# LMAT_AMT_MAG.net
KiCad netlist of a schematic drawn in Altium Designer
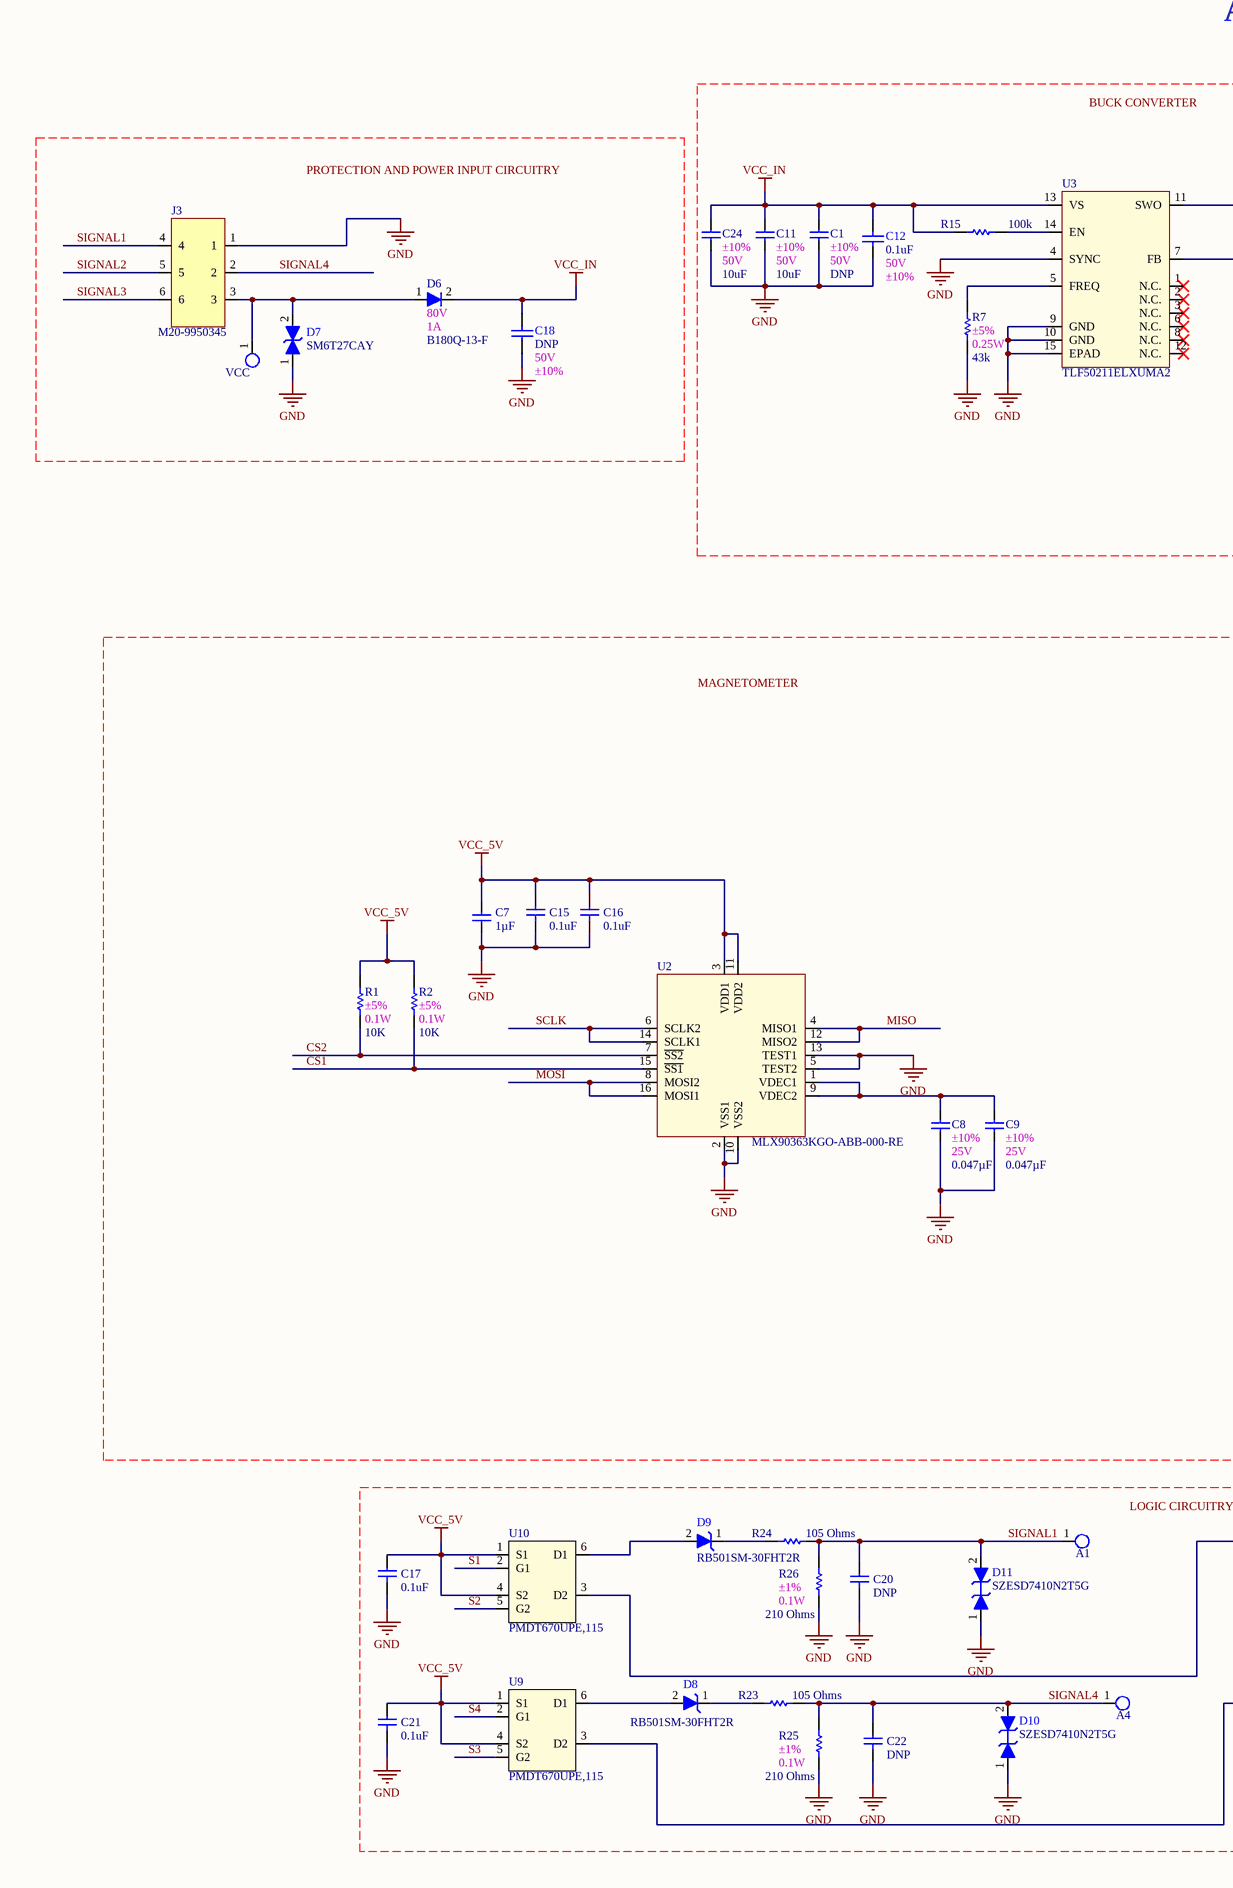
[diagram p0: LMAT_AMT_MAG.SchDoc, left]
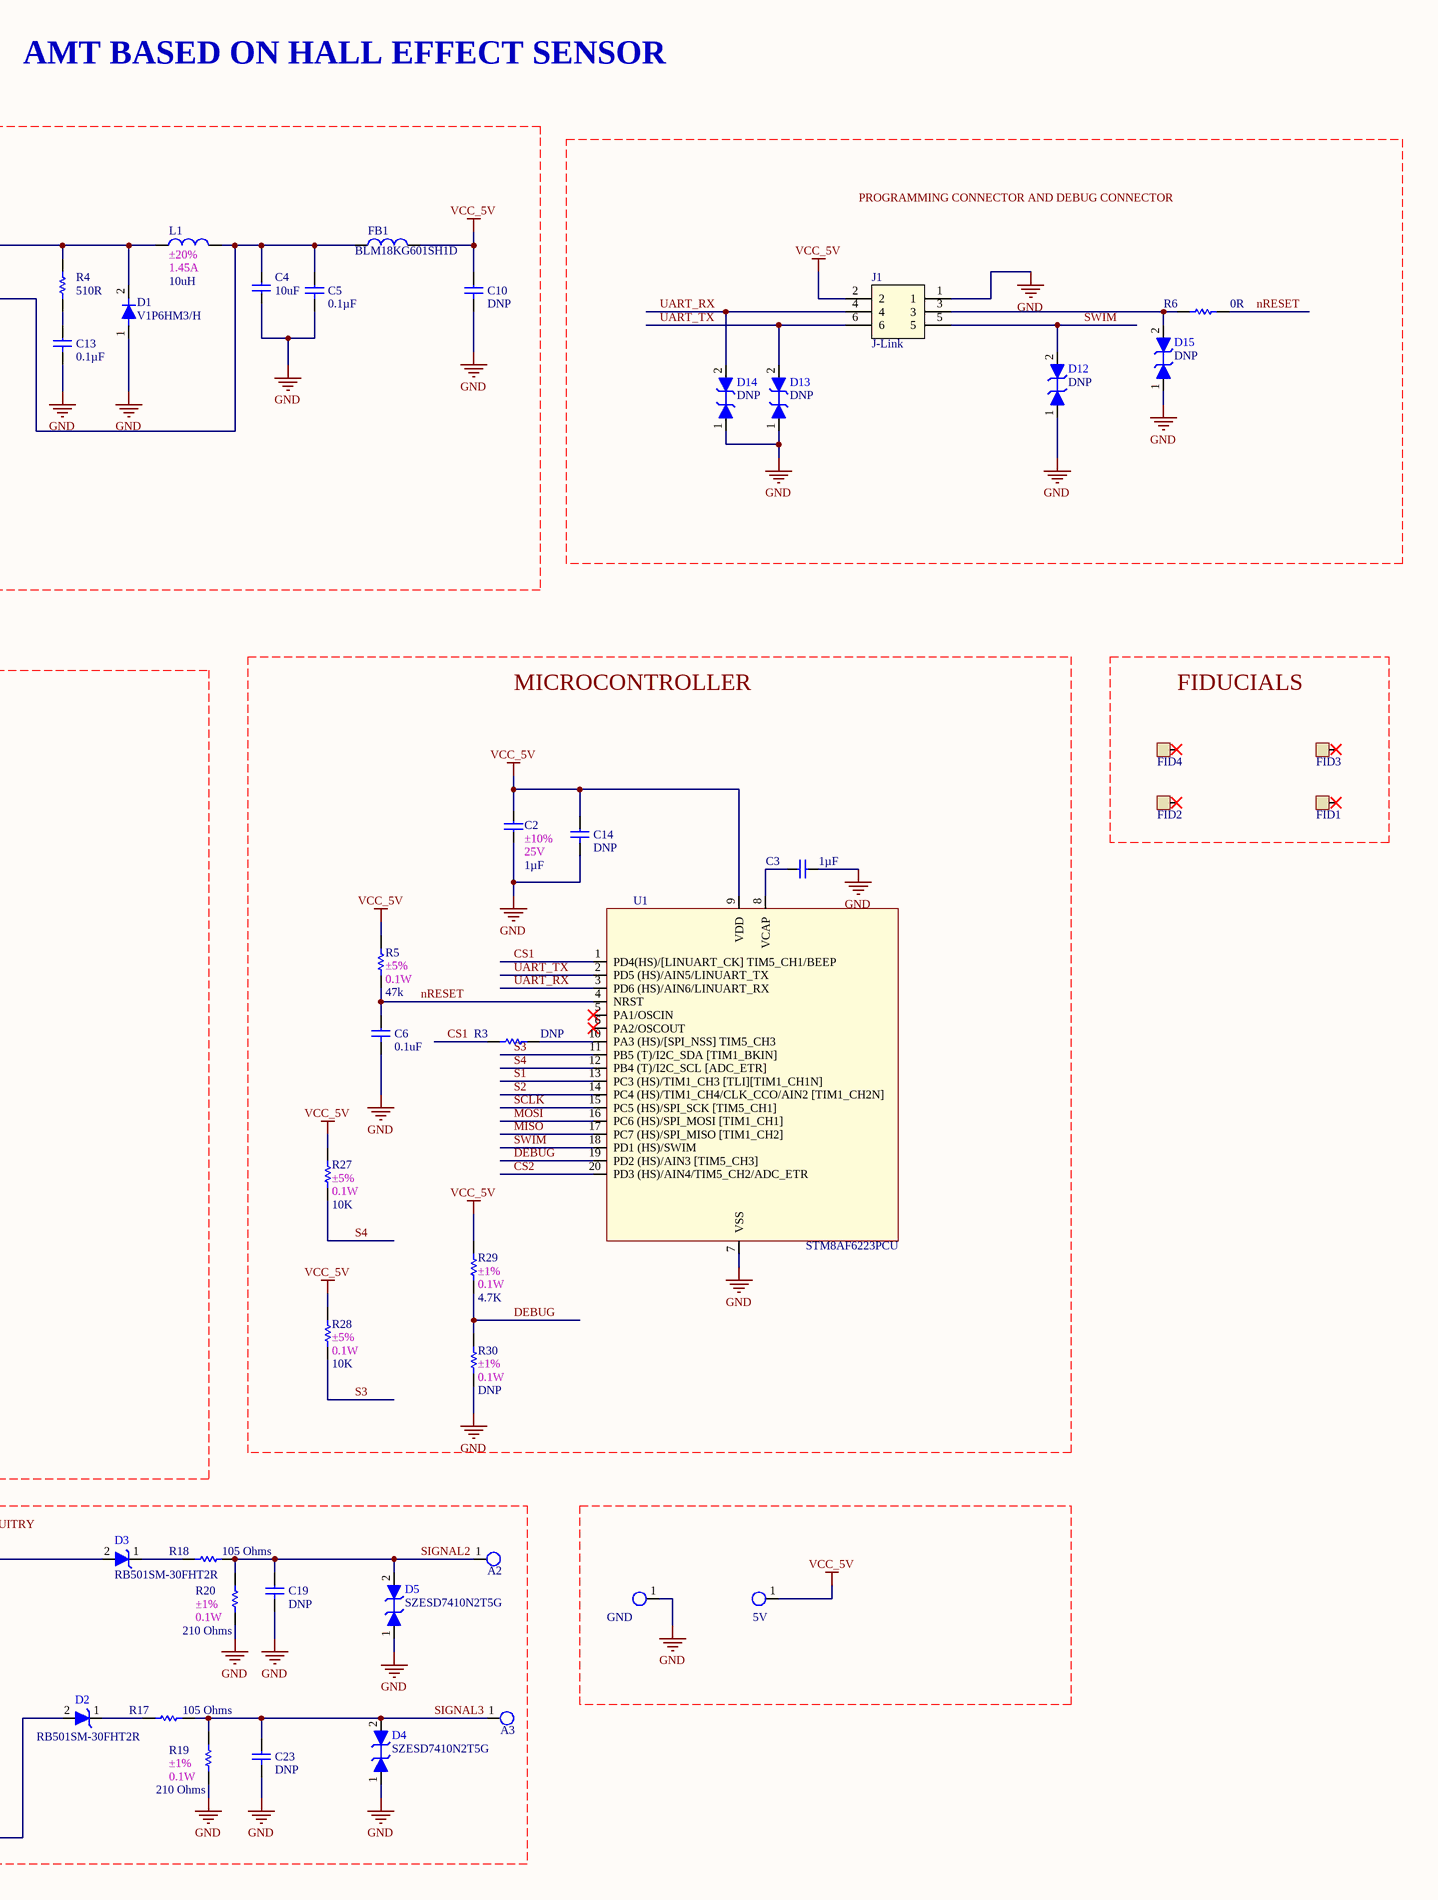
[diagram p1: LMAT_AMT_MAG.SchDoc, right]

(export (version "E")
  (design (tool "Eeschema 10.0.6"))
  (components
    (comp (ref "5V")
      (value "Test Point- 35mil")
      (footprint "Master_Library:TP_35M_DIA")
      (fields (field (name "INTERNAL PART NUMBER") "EMS-TP35MIL-S"))
      (libsource (lib "Integrated_Master_Library") (part "EMS-TP35MIL-S"))
    )
    (comp (ref "A1")
      (value "Test Point- 35mil")
      (footprint "Master_Library:TP_35M_DIA")
      (fields (field (name "INTERNAL PART NUMBER") "EMS-TP35MIL-S"))
      (libsource (lib "Integrated_Master_Library") (part "EMS-TP35MIL-S"))
    )
    (comp (ref "A2")
      (value "Test Point- 35mil")
      (footprint "Master_Library:TP_35M_DIA")
      (fields (field (name "INTERNAL PART NUMBER") "EMS-TP35MIL-S"))
      (libsource (lib "Integrated_Master_Library") (part "EMS-TP35MIL-S"))
    )
    (comp (ref "A3")
      (value "Test Point- 35mil")
      (footprint "Master_Library:TP_35M_DIA")
      (fields (field (name "INTERNAL PART NUMBER") "EMS-TP35MIL-S"))
      (libsource (lib "Integrated_Master_Library") (part "EMS-TP35MIL-S"))
    )
    (comp (ref "A4")
      (value "Test Point- 35mil")
      (footprint "Master_Library:TP_35M_DIA")
      (fields (field (name "INTERNAL PART NUMBER") "EMS-TP35MIL-S"))
      (libsource (lib "Integrated_Master_Library") (part "EMS-TP35MIL-S"))
    )
    (comp (ref "C1")
      (value "DNP")
      (footprint "Master_Library:SMDC1210")
      (description "CAP CER 10UF 50V X7R 1210")
      (fields
        (field (name "MANUFACTURER") "Taiyo Yuden")
        (field (name "VENDOR PART NUMBER") "587-6026-1-ND")
        (field (name "2ND AUXILIARY FIELD") "±10%")
        (field (name "1ST AUXILIARY FIELD") "50V")
      )
      (libsource (lib "Automobile-ML") (part "ECA10U0L50V0-SH"))
    )
    (comp (ref "C2")
      (value "1µF")
      (footprint "Masterlib_auto:SMDC0603")
      (description "CAP CER 1UF 25V X7R 0603")
      (fields
        (field (name "MANUFACTURER") "TDK Corporation")
        (field (name "VENDOR PART NUMBER") "445-173628-1-ND")
        (field (name "2ND AUXILIARY FIELD") "±10%")
        (field (name "1ST AUXILIARY FIELD") "25V")
      )
      (libsource (lib "Integrated_Master_Library (3)") (part "ECA1U00L25V0-SC"))
    )
    (comp (ref "C3")
      (value "1µF")
      (footprint "Masterlib_auto:SMDC0603")
      (description "CAP CER 1UF 25V X7R 0603")
      (fields
        (field (name "MANUFACTURER") "TDK Corporation")
        (field (name "VENDOR PART NUMBER") "445-173628-1-ND")
      )
      (libsource (lib "Integrated_Master_Library (3)") (part "ECA1U00L25V0-SC"))
    )
    (comp (ref "C4")
      (value "10uF")
      (footprint "Master_Library:SMDC1210")
      (description "CAP CER 10UF 50V X7R 1210")
      (fields (field (name "MANUFACTURER") "Taiyo Yuden") (field (name "VENDOR PART NUMBER") "587-6026-1-ND"))
      (libsource (lib "Automobile-ML") (part "ECA10U0L50V0-SH"))
    )
    (comp (ref "C5")
      (value "0.1µF")
      (footprint "Master_Library:SMDC0402")
      (description "CAP CER 0.1UF 16V X7R 0402")
      (fields
        (field (name "MANUFACTURER PART NUMBER") "GCM155R71C104KA55J")
        (field (name "MANUFACTURER") "Murata Electronics North America")
      )
      (libsource (lib "Automobile-ML") (part "ECA0U10L16V0-SB"))
    )
    (comp (ref "C6")
      (value "0.1uF")
      (footprint "Master_Library:SMDC0402")
      (description "CAP CER 0.1UF 16V X7R 0402")
      (fields
        (field (name "MANUFACTURER PART NUMBER") "GCM155R71C104KA55J")
        (field (name "MANUFACTURER") "Murata Electronics North America")
      )
      (libsource (lib "Automobile-ML") (part "ECA0U10L16V0-SB"))
    )
    (comp (ref "C7")
      (value "1µF")
      (footprint "Masterlib_auto:SMDC0603")
      (description "CAP CER 1UF 25V X7R 0603")
      (fields
        (field (name "MANUFACTURER") "TDK Corporation")
        (field (name "VENDOR PART NUMBER") "445-173628-1-ND")
      )
      (libsource (lib "Integrated_Master_Library (3)") (part "ECA1U00L25V0-SC"))
    )
    (comp (ref "C8")
      (value "0.047µF")
      (footprint "SMDC0402")
      (description "CAP CER 0.047UF 25V X7R 0402")
      (fields
        (field (name "MANUFACTURER") "Murata Electronics")
        (field (name "VENDOR PART NUMBER") "490-4760-1-ND")
        (field (name "2ND AUXILIARY FIELD") "±10%")
        (field (name "1ST AUXILIARY FIELD") "25V")
      )
      (libsource (lib "Automobile-ML") (part "ECA47N0L25V0-SB"))
    )
    (comp (ref "C9")
      (value "0.047µF")
      (footprint "SMDC0402")
      (description "CAP CER 0.047UF 25V X7R 0402")
      (fields
        (field (name "MANUFACTURER") "Murata Electronics")
        (field (name "VENDOR PART NUMBER") "490-4760-1-ND")
        (field (name "2ND AUXILIARY FIELD") "±10%")
        (field (name "1ST AUXILIARY FIELD") "25V")
      )
      (libsource (lib "Automobile-ML") (part "ECA47N0L25V0-SB"))
    )
    (comp (ref "C10")
      (value "DNP")
      (footprint "Master_Library:SMDC0402")
      (description "CAP CER 0.1UF 16V X7R 0402")
      (fields
        (field (name "MANUFACTURER PART NUMBER") "GCM155R71C104KA55J")
        (field (name "MANUFACTURER") "Murata Electronics North America")
      )
      (libsource (lib "Automobile-ML") (part "ECA0U10L16V0-SB"))
    )
    (comp (ref "C11")
      (value "10uF")
      (footprint "Master_Library:SMDC1210")
      (description "CAP CER 10UF 50V X7R 1210")
      (fields
        (field (name "MANUFACTURER") "Taiyo Yuden")
        (field (name "VENDOR PART NUMBER") "587-6026-1-ND")
        (field (name "2ND AUXILIARY FIELD") "±10%")
        (field (name "1ST AUXILIARY FIELD") "50V")
      )
      (libsource (lib "Automobile-ML") (part "ECA10U0L50V0-SH"))
    )
    (comp (ref "C12")
      (value "0.1uF")
      (footprint "Master_Library:SMDC0603")
      (description "CAP CER 0.1UF 50V 10% X7R 0603")
      (fields
        (field (name "MANUFACTURER PART NUMBER") "CGA3E2X7R1H104K080AA")
        (field (name "MANUFACTURER") "TDK Corporation")
        (field (name "1ST AUXILIARY FIELD") "50V")
        (field (name "2ND AUXILIARY FIELD") "±10%")
      )
      (libsource (lib "Integrated_Master_Library") (part "ECA0U10K50V0-SC"))
    )
    (comp (ref "C13")
      (value "0.1µF")
      (footprint "Master_Library:SMDC0402")
      (description "CAP CER 0.1UF 16V X7R 0402")
      (fields
        (field (name "MANUFACTURER PART NUMBER") "GCM155R71C104KA55J")
        (field (name "MANUFACTURER") "Murata Electronics North America")
      )
      (libsource (lib "Automobile-ML") (part "ECA0U10L16V0-SB"))
    )
    (comp (ref "C14")
      (value "DNP")
      (footprint "Master_Library:SMDC0402")
      (description "CAP CER 0.1UF 16V X7R 0402")
      (fields
        (field (name "MANUFACTURER PART NUMBER") "GCM155R71C104KA55J")
        (field (name "MANUFACTURER") "Murata Electronics North America")
      )
      (libsource (lib "Automobile-ML") (part "ECA0U10L16V0-SB"))
    )
    (comp (ref "C15")
      (value "0.1uF")
      (footprint "Master_Library:SMDC0402")
      (description "CAP CER 0.1UF 16V X7R 0402")
      (fields
        (field (name "MANUFACTURER PART NUMBER") "GCM155R71C104KA55J")
        (field (name "MANUFACTURER") "Murata Electronics North America")
      )
      (libsource (lib "Automobile-ML") (part "ECA0U10L16V0-SB"))
    )
    (comp (ref "C16")
      (value "0.1uF")
      (footprint "Master_Library:SMDC0402")
      (description "CAP CER 0.1UF 16V X7R 0402")
      (fields
        (field (name "MANUFACTURER PART NUMBER") "GCM155R71C104KA55J")
        (field (name "MANUFACTURER") "Murata Electronics North America")
      )
      (libsource (lib "Automobile-ML") (part "ECA0U10L16V0-SB"))
    )
    (comp (ref "C17")
      (value "0.1uF")
      (footprint "Master_Library:SMDC0402")
      (description "CAP CER 0.1UF 16V X7R 0402")
      (fields
        (field (name "MANUFACTURER PART NUMBER") "GCM155R71C104KA55J")
        (field (name "MANUFACTURER") "Murata Electronics North America")
      )
      (libsource (lib "Automobile-ML") (part "ECA0U10L16V0-SB"))
    )
    (comp (ref "C18")
      (value "DNP")
      (footprint "Master_Library:SMDC0603")
      (description "CAP CER 0.1UF 50V 10% X7R 0603")
      (fields
        (field (name "MANUFACTURER PART NUMBER") "CGA3E2X7R1H104K080AA")
        (field (name "MANUFACTURER") "TDK Corporation")
        (field (name "1ST AUXILIARY FIELD") "50V")
        (field (name "2ND AUXILIARY FIELD") "±10%")
      )
      (libsource (lib "Integrated_Master_Library") (part "ECA0U10K50V0-SC"))
    )
    (comp (ref "C19")
      (value "DNP")
      (footprint "Master_Library:SMDC0402")
      (description "CAP CER 0.1UF 16V X7R 0402")
      (fields
        (field (name "MANUFACTURER PART NUMBER") "GCM155R71C104KA55J")
        (field (name "MANUFACTURER") "Murata Electronics North America")
      )
      (libsource (lib "Automobile-ML") (part "ECA0U10L16V0-SB"))
    )
    (comp (ref "C20")
      (value "DNP")
      (footprint "Master_Library:SMDC0402")
      (description "CAP CER 0.1UF 16V X7R 0402")
      (fields
        (field (name "MANUFACTURER PART NUMBER") "GCM155R71C104KA55J")
        (field (name "MANUFACTURER") "Murata Electronics North America")
      )
      (libsource (lib "Automobile-ML") (part "ECA0U10L16V0-SB"))
    )
    (comp (ref "C21")
      (value "0.1uF")
      (footprint "Master_Library:SMDC0402")
      (description "CAP CER 0.1UF 16V X7R 0402")
      (fields
        (field (name "MANUFACTURER PART NUMBER") "GCM155R71C104KA55J")
        (field (name "MANUFACTURER") "Murata Electronics North America")
      )
      (libsource (lib "Automobile-ML") (part "ECA0U10L16V0-SB"))
    )
    (comp (ref "C22")
      (value "DNP")
      (footprint "Master_Library:SMDC0402")
      (description "CAP CER 0.1UF 16V X7R 0402")
      (fields
        (field (name "MANUFACTURER PART NUMBER") "GCM155R71C104KA55J")
        (field (name "MANUFACTURER") "Murata Electronics North America")
      )
      (libsource (lib "Automobile-ML") (part "ECA0U10L16V0-SB"))
    )
    (comp (ref "C23")
      (value "DNP")
      (footprint "Master_Library:SMDC0402")
      (description "CAP CER 0.1UF 16V X7R 0402")
      (fields
        (field (name "MANUFACTURER PART NUMBER") "GCM155R71C104KA55J")
        (field (name "MANUFACTURER") "Murata Electronics North America")
      )
      (libsource (lib "Automobile-ML") (part "ECA0U10L16V0-SB"))
    )
    (comp (ref "C24")
      (value "10uF")
      (footprint "Master_Library:SMDC1210")
      (description "CAP CER 10UF 50V X7R 1210")
      (fields
        (field (name "MANUFACTURER") "Taiyo Yuden")
        (field (name "VENDOR PART NUMBER") "587-6026-1-ND")
        (field (name "2ND AUXILIARY FIELD") "±10%")
        (field (name "1ST AUXILIARY FIELD") "50V")
      )
      (libsource (lib "Automobile-ML") (part "ECA10U0L50V0-SH"))
    )
    (comp (ref "D1")
      (value "V1P6HM3/H")
      (footprint "DIOM2213X07N")
      (description "DIODE SCHOTTKY 60V 1A MICROSMP")
      (fields
        (field (name "MANUFACTURER") "Vishay Semiconductor Diodes Division")
        (field (name "INTERNAL PART NUMBER") "EDDVS1A0060V0-S")
      )
      (libsource (lib "Automobile-ML") (part "EDDVS1A0060V0-S"))
    )
    (comp (ref "D2")
      (value "RB501SM-30FHT2R")
      (footprint "Master_Library:SOD1700X70N-V2")
      (description "Diode Schottky 30V 100mA Surface Mount EMD2")
      (fields
        (field (name "MANUFACTURER") "Rohm Semiconductor")
        (field (name "INTERNAL PART NUMBER") "EDDR0A1030V0-S")
      )
      (libsource (lib "Integrated_Master_Library (3)") (part "EDDR0A1030V0-S"))
    )
    (comp (ref "D3")
      (value "RB501SM-30FHT2R")
      (footprint "Master_Library:SOD1700X70N-V2")
      (description "Diode Schottky 30V 100mA Surface Mount EMD2")
      (fields
        (field (name "MANUFACTURER") "Rohm Semiconductor")
        (field (name "INTERNAL PART NUMBER") "EDDR0A1030V0-S")
      )
      (libsource (lib "Integrated_Master_Library (3)") (part "EDDR0A1030V0-S"))
    )
    (comp (ref "D4")
      (value "SZESD7410N2T5G")
      (footprint "Masterlib_auto:DFN65P100X65X45-2N")
      (description "TVS DIODE 8V 20V 2X2DFN")
      (fields
        (field (name "MANUFACTURER") "ON Semiconductor")
        (field (name "INTERNAL PART NUMBER") "EDDOS16A010V0-S")
      )
      (libsource (lib "Automobile-ML") (part "EDDOS16A010V0-S"))
    )
    (comp (ref "D5")
      (value "SZESD7410N2T5G")
      (footprint "Masterlib_auto:DFN65P100X65X45-2N")
      (description "TVS DIODE 8V 20V 2X2DFN")
      (fields
        (field (name "MANUFACTURER") "ON Semiconductor")
        (field (name "INTERNAL PART NUMBER") "EDDOS16A010V0-S")
      )
      (libsource (lib "Automobile-ML") (part "EDDOS16A010V0-S"))
    )
    (comp (ref "D6")
      (value "B180Q-13-F")
      (footprint "DO460X292X240-2N")
      (description "DIODE SCHOTTKY 80V 1A SMA")
      (fields
        (field (name "MANUFACTURER") "Diodes Incorporated")
        (field (name "INTERNAL PART NUMBER") "EDDDI1A0080V0-S")
        (field (name "1ST AUXILIARY FIELD") "80V")
        (field (name "2ND AUXILIARY FIELD") "1A")
      )
      (libsource (lib "Automobile-ML") (part "EDDDI1A0080V0-S"))
    )
    (comp (ref "D7")
      (value "SM6T27CAY")
      (footprint "Master_Library:DIOM4336X26B")
      (description "TVS DIODE 23.1V 48.3V SMB")
      (fields
        (field (name "MANUFACTURER") "STMicroelectronics")
        (field (name "INTERNAL PART NUMBER") "EDDST83A025V7-S")
      )
      (libsource (lib "Integrated_Master_Library") (part "EDDST83A025V7-S"))
    )
    (comp (ref "D8")
      (value "RB501SM-30FHT2R")
      (footprint "Master_Library:SOD1700X70N-V2")
      (description "Diode Schottky 30V 100mA Surface Mount EMD2")
      (fields
        (field (name "MANUFACTURER") "Rohm Semiconductor")
        (field (name "INTERNAL PART NUMBER") "EDDR0A1030V0-S")
      )
      (libsource (lib "Integrated_Master_Library (3)") (part "EDDR0A1030V0-S"))
    )
    (comp (ref "D9")
      (value "RB501SM-30FHT2R")
      (footprint "Master_Library:SOD1700X70N-V2")
      (description "Diode Schottky 30V 100mA Surface Mount EMD2")
      (fields
        (field (name "MANUFACTURER") "Rohm Semiconductor")
        (field (name "INTERNAL PART NUMBER") "EDDR0A1030V0-S")
      )
      (libsource (lib "Integrated_Master_Library (3)") (part "EDDR0A1030V0-S"))
    )
    (comp (ref "D10")
      (value "SZESD7410N2T5G")
      (footprint "Masterlib_auto:DFN65P100X65X45-2N")
      (description "TVS DIODE 8V 20V 2X2DFN")
      (fields
        (field (name "MANUFACTURER") "ON Semiconductor")
        (field (name "INTERNAL PART NUMBER") "EDDOS16A010V0-S")
      )
      (libsource (lib "Automobile-ML") (part "EDDOS16A010V0-S"))
    )
    (comp (ref "D11")
      (value "SZESD7410N2T5G")
      (footprint "Masterlib_auto:DFN65P100X65X45-2N")
      (description "TVS DIODE 8V 20V 2X2DFN")
      (fields
        (field (name "MANUFACTURER") "ON Semiconductor")
        (field (name "INTERNAL PART NUMBER") "EDDOS16A010V0-S")
      )
      (libsource (lib "Automobile-ML") (part "EDDOS16A010V0-S"))
    )
    (comp (ref "D12")
      (value "DNP")
      (footprint "Master_Library:DFN65P100X65X45-2N")
      (description "TVS DIODE 8V 20V 2X2DFN")
      (fields
        (field (name "MANUFACTURER PART NUMBER") "SZESD7410N2T5G")
        (field (name "MANUFACTURER") "ON Semiconductor")
      )
      (libsource (lib "Automobile-ML") (part "EDDOS16A010V0-S"))
    )
    (comp (ref "D13")
      (value "DNP")
      (footprint "Master_Library:DFN65P100X65X45-2N")
      (description "TVS DIODE 8V 20V 2X2DFN")
      (fields
        (field (name "MANUFACTURER PART NUMBER") "SZESD7410N2T5G")
        (field (name "MANUFACTURER") "ON Semiconductor")
      )
      (libsource (lib "Automobile-ML") (part "EDDOS16A010V0-S"))
    )
    (comp (ref "D14")
      (value "DNP")
      (footprint "Master_Library:DFN65P100X65X45-2N")
      (description "TVS DIODE 8V 20V 2X2DFN")
      (fields
        (field (name "MANUFACTURER PART NUMBER") "SZESD7410N2T5G")
        (field (name "MANUFACTURER") "ON Semiconductor")
      )
      (libsource (lib "Automobile-ML") (part "EDDOS16A010V0-S"))
    )
    (comp (ref "D15")
      (value "DNP")
      (footprint "Master_Library:DFN65P100X65X45-2N")
      (description "TVS DIODE 8V 20V 2X2DFN")
      (fields
        (field (name "MANUFACTURER PART NUMBER") "SZESD7410N2T5G")
        (field (name "MANUFACTURER") "ON Semiconductor")
      )
      (libsource (lib "Automobile-ML") (part "EDDOS16A010V0-S"))
    )
    (comp (ref "FB1")
      (value "BLM18KG601SH1D")
      (footprint "Master_Library:SMDL0603")
      (description "FERRITE BEAD 600 OHM 0603 1LN")
      (fields
        (field (name "MANUFACTURER") "Murata Electronics North America")
        (field (name "VENDOR PART NUMBER") "490-13259-1-ND")
      )
      (libsource (lib "Automobile-ML") (part "EIN600R1A30-S"))
    )
    (comp (ref "FID1")
      (value "FID40X40")
      (footprint "Master_Library:FID40X40")
      (libsource (lib "Integrated_Master_Library") (part "FID_40X40"))
    )
    (comp (ref "FID2")
      (value "FID40X40")
      (footprint "Master_Library:FID40X40")
      (libsource (lib "Integrated_Master_Library") (part "FID_40X40"))
    )
    (comp (ref "FID3")
      (value "FID40X40")
      (footprint "Master_Library:FID40X40")
      (libsource (lib "Integrated_Master_Library") (part "FID_40X40"))
    )
    (comp (ref "FID4")
      (value "FID40X40")
      (footprint "Master_Library:FID40X40")
      (libsource (lib "Integrated_Master_Library") (part "FID_40X40"))
    )
    (comp (ref "GND")
      (value "Test Point- 35mil")
      (footprint "Master_Library:TP_35M_DIA")
      (fields (field (name "INTERNAL PART NUMBER") "EMS-TP35MIL-S"))
      (libsource (lib "Integrated_Master_Library") (part "EMS-TP35MIL-S"))
    )
    (comp (ref "J1")
      (value "J-LINK 6-PIN NEEDLE ADAPTER")
      (footprint "PRG_8.06.16 J-LINK 6-PIN NEEDLE ADAPTER")
      (fields
        (field (name "INTERNAL PART NUMBER") "EMS-8.06.16 J-LINK 6-PIN NEEDLE ADAPTER")
        (field (name "MANUFACTURER") "Segger Microcontroller Systems")
        (field (name "VENDOR PART NUMBER") "899-1051-ND")
        (field (name "1ST AUXILIARY FIELD") "J-Link")
      )
      (libsource (lib "Integrated_Master_Library") (part "EMS-8.06.16 J-LINK 6-PIN NEEDLE ADAPTER"))
    )
    (comp (ref "J3")
      (value "CONN HEADER R/A 6POS 2.54MM")
      (footprint "Masterlib_auto:HDRRA6W86P254_2X3_1344X254X528P_Modified")
      (fields
        (field (name "MANUFACTURER") "Harwin Inc.")
        (field (name "INTERNAL PART NUMBER") "ECN-M20-9950345-0003-0060")
        (field (name "VENDOR PART NUMBER") "952-2092-ND")
        (field (name "MANUFACTURER PART NUMBER") "M20-9950345")
      )
      (libsource (lib "Automobile-ML") (part "ECN-M20-9950345-0003-0060"))
    )
    (comp (ref "L1")
      (value "10uH")
      (footprint "IND_NRS5030T3R3MMGJ")
      (description "FIXED IND 10UH 1.45A 144 MOHM")
      (fields
        (field (name "MANUFACTURER") "Taiyo Yuden")
        (field (name "VENDOR PART NUMBER") "587-3594-1-ND")
        (field (name "2ND AUXILIARY FIELD") "±20%")
        (field (name "1ST AUXILIARY FIELD") "1.45A")
      )
      (libsource (lib "Automobile-ML") (part "EIN10U0N1A45-S"))
    )
    (comp (ref "R1")
      (value "10K")
      (footprint "Master_Library:SMDR0402")
      (description "RES SMD 10K OHM 5% 1/10W 0402")
      (fields
        (field (name "MANUFACTURER") "Panasonic Electronic Components")
        (field (name "VENDOR PART NUMBER") "P10KJCT-ND")
        (field (name "2ND AUXILIARY FIELD") "±5%")
        (field (name "1ST AUXILIARY FIELD") "0.1W")
      )
      (libsource (lib "Automobile-ML") (part "ERE10K0K110-SB"))
    )
    (comp (ref "R2")
      (value "10K")
      (footprint "Master_Library:SMDR0402")
      (description "RES SMD 10K OHM 5% 1/10W 0402")
      (fields
        (field (name "MANUFACTURER") "Panasonic Electronic Components")
        (field (name "VENDOR PART NUMBER") "P10KJCT-ND")
        (field (name "2ND AUXILIARY FIELD") "±5%")
        (field (name "1ST AUXILIARY FIELD") "0.1W")
      )
      (libsource (lib "Automobile-ML") (part "ERE10K0K110-SB"))
    )
    (comp (ref "R3")
      (value "DNP")
      (footprint "Masterlib_auto:SMDR0402")
      (description "RES SMD 0 OHM JUMPER 1/10W 0402")
      (fields
        (field (name "MANUFACTURER") "Panasonic Electronic Components")
        (field (name "VENDOR PART NUMBER") "P0.0JCT-ND")
      )
      (libsource (lib "Automobile-ML") (part "ERE0R00R110-SB"))
    )
    (comp (ref "R4")
      (value "510R")
      (footprint "Masterlib_auto:SMDR0402")
      (description "RES SMD 510 OHM 5% 1/10W 0402")
      (fields
        (field (name "MANUFACTURER") "Panasonic Electronic Components")
        (field (name "VENDOR PART NUMBER") "P510JCT-ND")
      )
      (libsource (lib "Automobile-ML") (part "ERE510RK110-SB"))
    )
    (comp (ref "R5")
      (value "47k")
      (footprint "SMDR0402")
      (description "RES SMD 47K OHM 5% 1/10W 0402")
      (fields
        (field (name "MANUFACTURER") "Panasonic Electronic Components")
        (field (name "VENDOR PART NUMBER") "P47KJCT-ND")
        (field (name "2ND AUXILIARY FIELD") "±5%")
        (field (name "1ST AUXILIARY FIELD") "0.1W")
      )
      (libsource (lib "Automobile-ML") (part "ERE47K0K110-SB"))
    )
    (comp (ref "R6")
      (value "0R")
      (footprint "SMDR0402")
      (description "RES SMD 0 OHM JUMPER 1/10W 0402")
      (fields
        (field (name "MANUFACTURER") "Panasonic Electronic Components")
        (field (name "VENDOR PART NUMBER") "P0.0JCT-ND")
      )
      (libsource (lib "Automobile-ML") (part "ERE0R00R110-SB"))
    )
    (comp (ref "R7")
      (value "43k")
      (footprint "SMDR0805")
      (description "RES 43K OHM 5% 1/4W 0805")
      (fields
        (field (name "MANUFACTURER") "KOA Speer Electronics, Inc.")
        (field (name "VENDOR PART NUMBER") "2019-RK73B2ATTD433JCT-ND")
        (field (name "2ND AUXILIARY FIELD") "±5%")
        (field (name "1ST AUXILIARY FIELD") "0.25W")
      )
      (libsource (lib "Automobile-ML") (part "ERE43K0K140-SE"))
    )
    (comp (ref "R15")
      (value "100k")
      (footprint "Masterlib_auto:SMDR0402")
      (description "RES SMD 100K OHM 1% 1/10W 0402")
      (fields
        (field (name "MANUFACTURER") "Panasonic Electronic Components")
        (field (name "VENDOR PART NUMBER") "P100KLCT-ND")
      )
      (libsource (lib "Automobile-ML") (part "ERE100KG110-SB"))
    )
    (comp (ref "R17")
      (value "105 Ohms")
      (footprint "Masterlib_auto:SMDR0603")
      (description "RES SMD 105 OHM 1% 1/10W 0603")
      (fields
        (field (name "MANUFACTURER") "Panasonic Electronic Components")
        (field (name "VENDOR PART NUMBER") "P105HCT-ND")
      )
      (libsource (lib "Automobile-ML") (part "ERE105RG110-SC"))
    )
    (comp (ref "R18")
      (value "105 Ohms")
      (footprint "Masterlib_auto:SMDR0603")
      (description "RES SMD 105 OHM 1% 1/10W 0603")
      (fields
        (field (name "MANUFACTURER") "Panasonic Electronic Components")
        (field (name "VENDOR PART NUMBER") "P105HCT-ND")
      )
      (libsource (lib "Automobile-ML") (part "ERE105RG110-SC"))
    )
    (comp (ref "R19")
      (value "210 Ohms")
      (footprint "Masterlib_auto:SMDR0603")
      (description "RES SMD 210 OHM 1% 1/10W 0603")
      (fields
        (field (name "MANUFACTURER") "Panasonic Electronic Components")
        (field (name "VENDOR PART NUMBER") "P210HCT-ND")
        (field (name "2ND AUXILIARY FIELD") "±1%")
        (field (name "1ST AUXILIARY FIELD") "0.1W")
      )
      (libsource (lib "Automobile-ML") (part "ERE210RG110-SC"))
    )
    (comp (ref "R20")
      (value "210 Ohms")
      (footprint "Masterlib_auto:SMDR0603")
      (description "RES SMD 210 OHM 1% 1/10W 0603")
      (fields
        (field (name "MANUFACTURER") "Panasonic Electronic Components")
        (field (name "VENDOR PART NUMBER") "P210HCT-ND")
        (field (name "2ND AUXILIARY FIELD") "±1%")
        (field (name "1ST AUXILIARY FIELD") "0.1W")
      )
      (libsource (lib "Automobile-ML") (part "ERE210RG110-SC"))
    )
    (comp (ref "R23")
      (value "105 Ohms")
      (footprint "Masterlib_auto:SMDR0603")
      (description "RES SMD 105 OHM 1% 1/10W 0603")
      (fields
        (field (name "MANUFACTURER") "Panasonic Electronic Components")
        (field (name "VENDOR PART NUMBER") "P105HCT-ND")
      )
      (libsource (lib "Automobile-ML") (part "ERE105RG110-SC"))
    )
    (comp (ref "R24")
      (value "105 Ohms")
      (footprint "Masterlib_auto:SMDR0603")
      (description "RES SMD 105 OHM 1% 1/10W 0603")
      (fields
        (field (name "MANUFACTURER") "Panasonic Electronic Components")
        (field (name "VENDOR PART NUMBER") "P105HCT-ND")
      )
      (libsource (lib "Automobile-ML") (part "ERE105RG110-SC"))
    )
    (comp (ref "R25")
      (value "210 Ohms")
      (footprint "Masterlib_auto:SMDR0603")
      (description "RES SMD 210 OHM 1% 1/10W 0603")
      (fields
        (field (name "MANUFACTURER") "Panasonic Electronic Components")
        (field (name "VENDOR PART NUMBER") "P210HCT-ND")
        (field (name "2ND AUXILIARY FIELD") "±1%")
        (field (name "1ST AUXILIARY FIELD") "0.1W")
      )
      (libsource (lib "Automobile-ML") (part "ERE210RG110-SC"))
    )
    (comp (ref "R26")
      (value "210 Ohms")
      (footprint "Masterlib_auto:SMDR0603")
      (description "RES SMD 210 OHM 1% 1/10W 0603")
      (fields
        (field (name "MANUFACTURER") "Panasonic Electronic Components")
        (field (name "VENDOR PART NUMBER") "P210HCT-ND")
        (field (name "2ND AUXILIARY FIELD") "±1%")
        (field (name "1ST AUXILIARY FIELD") "0.1W")
      )
      (libsource (lib "Automobile-ML") (part "ERE210RG110-SC"))
    )
    (comp (ref "R27")
      (value "10K")
      (footprint "Masterlib_auto:SMDR0402")
      (description "RES SMD 10K OHM 5% 1/10W 0402")
      (fields
        (field (name "MANUFACTURER") "Panasonic Electronic Components")
        (field (name "VENDOR PART NUMBER") "P10KJCT-ND")
        (field (name "2ND AUXILIARY FIELD") "±5%")
        (field (name "1ST AUXILIARY FIELD") "0.1W")
      )
      (libsource (lib "Automobile-ML") (part "ERE10K0K110-SB"))
    )
    (comp (ref "R28")
      (value "10K")
      (footprint "Masterlib_auto:SMDR0402")
      (description "RES SMD 10K OHM 5% 1/10W 0402")
      (fields
        (field (name "MANUFACTURER") "Panasonic Electronic Components")
        (field (name "VENDOR PART NUMBER") "P10KJCT-ND")
        (field (name "2ND AUXILIARY FIELD") "±5%")
        (field (name "1ST AUXILIARY FIELD") "0.1W")
      )
      (libsource (lib "Automobile-ML") (part "ERE10K0K110-SB"))
    )
    (comp (ref "R29")
      (value "4.7K")
      (footprint "Masterlib_auto:SMDR0402")
      (description "RES SMD 4.7K OHM 1% 1/10W 0402")
      (fields
        (field (name "MANUFACTURER") "Panasonic Electronic Components")
        (field (name "VENDOR PART NUMBER") "P4.70KLCT-ND")
        (field (name "2ND AUXILIARY FIELD") "±1%")
        (field (name "1ST AUXILIARY FIELD") "0.1W")
      )
      (libsource (lib "Automobile-ML") (part "ERE4K70G110-SB"))
    )
    (comp (ref "R30")
      (value "DNP")
      (footprint "Masterlib_auto:SMDR0402")
      (description "RES SMD 4.7K OHM 1% 1/10W 0402")
      (fields
        (field (name "MANUFACTURER") "Panasonic Electronic Components")
        (field (name "VENDOR PART NUMBER") "P4.70KLCT-ND")
        (field (name "2ND AUXILIARY FIELD") "±1%")
        (field (name "1ST AUXILIARY FIELD") "0.1W")
      )
      (libsource (lib "Automobile-ML") (part "ERE4K70G110-SB"))
    )
    (comp (ref "U1")
      (value "STM8AF6223PCU")
      (footprint "Masterlib_auto:SOP65P640X120-20N")
      (description "IC MCU 8BIT 8KB FLASH 20TSSOP")
      (fields
        (field (name "MANUFACTURER") "STMicroelectronics")
        (field (name "INTERNAL PART NUMBER") "EICSTMTSSOP-20-1691")
      )
      (libsource (lib "Integrated_Master_Library (3)") (part "EICSTMTSSOP-20-1691"))
    )
    (comp (ref "U2")
      (value "MLX90363KGO-ABB-000-RE")
      (footprint "Master_Library:SOP65P640X120-16N")
      (description "SENSOR HALL EFFECT SPI 16TSSOP")
      (fields
        (field (name "MANUFACTURER") "Melexis Technologies NV")
        (field (name "INTERNAL PART NUMBER") "EICMTTSSOP-16-1690")
      )
      (libsource (lib "Integrated_Master_Library") (part "EICMTTSSOP-16-1690"))
    )
    (comp (ref "U3")
      (value "TLF50211ELXUMA2")
      (footprint "SOP65P600X170_HS-15N")
      (description "IC REG DC/DC CONVERTER")
      (fields
        (field (name "MANUFACTURER") "Infineon Technologies")
        (field (name "INTERNAL PART NUMBER") "EICITLSSOP-14-1747")
      )
      (libsource (lib "Automobile-ML") (part "EICITLSSOP-14-1747"))
    )
    (comp (ref "U9")
      (value "PMDT670UPE,115")
      (footprint "Masterlib_auto:SOTFL50P160X60-6N")
      (description "MOSFET 2P-CH 20V 0.55A SOT666")
      (fields
        (field (name "MANUFACTURER") "Nexperia USA Inc.")
        (field (name "INTERNAL PART NUMBER") "EICNUSOT666-06-0004")
      )
      (libsource (lib "Automobile-ML") (part "EICNUSOT666-06-0004"))
    )
    (comp (ref "U10")
      (value "PMDT670UPE,115")
      (footprint "Masterlib_auto:SOTFL50P160X60-6N")
      (description "MOSFET 2P-CH 20V 0.55A SOT666")
      (fields
        (field (name "MANUFACTURER") "Nexperia USA Inc.")
        (field (name "INTERNAL PART NUMBER") "EICNUSOT666-06-0004")
      )
      (libsource (lib "Automobile-ML") (part "EICNUSOT666-06-0004"))
    )
    (comp (ref "VCC")
      (value "Test Point- 35mil")
      (footprint "Master_Library:TP_35M_DIA")
      (fields (field (name "INTERNAL PART NUMBER") "EMS-TP35MIL-S"))
      (libsource (lib "Integrated_Master_Library") (part "EMS-TP35MIL-S"))
    )
  )
  (nets
    (net (code "1") (name "/CS1") (class "Default")
      (node (ref "R2") (pin "1") (pinfunction "1_1") (pintype "passive"))
      (node (ref "R3") (pin "1") (pinfunction "1_1") (pintype "passive"))
      (node (ref "U1") (pin "1") (pinfunction "PD4(HS)/[LINUART_CK]_TIM5_CH1/BEEP_1") (pintype "passive"))
      (node (ref "U2") (pin "15") (pinfunction "~{SS1}_15") (pintype "passive"))
    )
    (net (code "2") (name "/CS2") (class "Default")
      (node (ref "R1") (pin "1") (pinfunction "1_1") (pintype "passive"))
      (node (ref "U1") (pin "20") (pinfunction "PD3_(HS)/AIN4/TIM5_CH2/ADC_ETR_20") (pintype "passive"))
      (node (ref "U2") (pin "7") (pinfunction "~{SS2}_7") (pintype "passive"))
    )
    (net (code "3") (name "/DEBUG") (class "Default")
      (node (ref "R29") (pin "1") (pinfunction "1_1") (pintype "passive"))
      (node (ref "R30") (pin "2") (pinfunction "2_2") (pintype "passive"))
      (node (ref "U1") (pin "19") (pinfunction "PD2_(HS)/AIN3_[TIM5_CH3]_19") (pintype "passive"))
    )
    (net (code "4") (name "/MISO") (class "Default")
      (node (ref "U1") (pin "17") (pinfunction "PC7_(HS)/SPI_MISO_[TIM1_CH2]_17") (pintype "passive"))
      (node (ref "U2") (pin "12") (pinfunction "MISO2_12") (pintype "passive"))
      (node (ref "U2") (pin "4") (pinfunction "MISO1_4") (pintype "passive"))
    )
    (net (code "5") (name "/MOSI") (class "Default")
      (node (ref "U1") (pin "16") (pinfunction "PC6_(HS)/SPI_MOSI_[TIM1_CH1]_16") (pintype "passive"))
      (node (ref "U2") (pin "16") (pinfunction "MOSI1_16") (pintype "passive"))
      (node (ref "U2") (pin "8") (pinfunction "MOSI2_8") (pintype "passive"))
    )
    (net (code "6") (name "/S1") (class "Default")
      (node (ref "U1") (pin "13") (pinfunction "PC3_(HS)/TIM1_CH3_[TLI][TIM1_CH1N]_13") (pintype "passive"))
      (node (ref "U10") (pin "2") (pinfunction "G1_2") (pintype "passive"))
    )
    (net (code "7") (name "/S2") (class "Default")
      (node (ref "U1") (pin "14") (pinfunction "PC4_(HS)/TIM1_CH4/CLK_CCO/AIN2_[TIM1_CH2N]_14") (pintype "passive"))
      (node (ref "U10") (pin "5") (pinfunction "G2_5") (pintype "passive"))
    )
    (net (code "8") (name "/S3") (class "Default")
      (node (ref "R28") (pin "1") (pinfunction "1_1") (pintype "passive"))
      (node (ref "U1") (pin "11") (pinfunction "PB5_(T)/I2C_SDA_[TIM1_BKIN]_11") (pintype "passive"))
      (node (ref "U9") (pin "5") (pinfunction "G2_5") (pintype "passive"))
    )
    (net (code "9") (name "/S4") (class "Default")
      (node (ref "R27") (pin "1") (pinfunction "1_1") (pintype "passive"))
      (node (ref "U1") (pin "12") (pinfunction "PB4_(T)/I2C_SCL_[ADC_ETR]_12") (pintype "passive"))
      (node (ref "U9") (pin "2") (pinfunction "G1_2") (pintype "passive"))
    )
    (net (code "10") (name "/SCLK") (class "Default")
      (node (ref "U1") (pin "15") (pinfunction "PC5_(HS)/SPI_SCK_[TIM5_CH1]_15") (pintype "passive"))
      (node (ref "U2") (pin "14") (pinfunction "SCLK1_14") (pintype "passive"))
      (node (ref "U2") (pin "6") (pinfunction "SCLK2_6") (pintype "passive"))
    )
    (net (code "11") (name "/SIGNAL1") (class "Default")
      (node (ref "A1") (pin "1") (pinfunction "1_1") (pintype "passive"))
      (node (ref "C20") (pin "2") (pinfunction "2_2") (pintype "passive"))
      (node (ref "D11") (pin "2") (pinfunction "CATHODE_2") (pintype "passive"))
      (node (ref "J3") (pin "4") (pinfunction "4_4") (pintype "passive"))
      (node (ref "R24") (pin "2") (pinfunction "2_2") (pintype "passive"))
      (node (ref "R26") (pin "1") (pinfunction "1_1") (pintype "passive"))
    )
    (net (code "12") (name "/SIGNAL2") (class "Default")
      (node (ref "A2") (pin "1") (pinfunction "1_1") (pintype "passive"))
      (node (ref "C19") (pin "2") (pinfunction "2_2") (pintype "passive"))
      (node (ref "D5") (pin "2") (pinfunction "CATHODE_2") (pintype "passive"))
      (node (ref "J3") (pin "5") (pinfunction "5_5") (pintype "passive"))
      (node (ref "R18") (pin "2") (pinfunction "2_2") (pintype "passive"))
      (node (ref "R20") (pin "1") (pinfunction "1_1") (pintype "passive"))
    )
    (net (code "13") (name "/SIGNAL3") (class "Default")
      (node (ref "A3") (pin "1") (pinfunction "1_1") (pintype "passive"))
      (node (ref "C23") (pin "2") (pinfunction "2_2") (pintype "passive"))
      (node (ref "D4") (pin "2") (pinfunction "CATHODE_2") (pintype "passive"))
      (node (ref "J3") (pin "6") (pinfunction "6_6") (pintype "passive"))
      (node (ref "R17") (pin "2") (pinfunction "2_2") (pintype "passive"))
      (node (ref "R19") (pin "1") (pinfunction "1_1") (pintype "passive"))
    )
    (net (code "14") (name "/SIGNAL4") (class "Default")
      (node (ref "A4") (pin "1") (pinfunction "1_1") (pintype "passive"))
      (node (ref "C22") (pin "2") (pinfunction "2_2") (pintype "passive"))
      (node (ref "D10") (pin "2") (pinfunction "CATHODE_2") (pintype "passive"))
      (node (ref "J3") (pin "2") (pinfunction "2_2") (pintype "passive"))
      (node (ref "R23") (pin "2") (pinfunction "2_2") (pintype "passive"))
      (node (ref "R25") (pin "1") (pinfunction "1_1") (pintype "passive"))
    )
    (net (code "15") (name "/SWIM") (class "Default")
      (node (ref "D12") (pin "2") (pinfunction "CATHODE_2") (pintype "passive"))
      (node (ref "J1") (pin "5") (pinfunction "5_5") (pintype "passive"))
      (node (ref "U1") (pin "18") (pinfunction "PD1_(HS)/SWIM_18") (pintype "passive"))
    )
    (net (code "16") (name "/UART_RX") (class "Default")
      (node (ref "D14") (pin "2") (pinfunction "CATHODE_2") (pintype "passive"))
      (node (ref "J1") (pin "4") (pinfunction "4_4") (pintype "passive"))
      (node (ref "U1") (pin "3") (pinfunction "PD6_(HS)/AIN6/LINUART_RX_3") (pintype "passive"))
    )
    (net (code "17") (name "/UART_TX") (class "Default")
      (node (ref "D13") (pin "2") (pinfunction "CATHODE_2") (pintype "passive"))
      (node (ref "J1") (pin "6") (pinfunction "6_6") (pintype "passive"))
      (node (ref "U1") (pin "2") (pinfunction "PD5_(HS)/AIN5/LINUART_TX_2") (pintype "passive"))
    )
    (net (code "18") (name "/nRESET") (class "Default")
      (node (ref "C6") (pin "2") (pinfunction "2_2") (pintype "passive"))
      (node (ref "R5") (pin "1") (pinfunction "1_1") (pintype "passive"))
      (node (ref "R6") (pin "2") (pinfunction "2_2") (pintype "passive"))
      (node (ref "U1") (pin "4") (pinfunction "NRST_4") (pintype "passive"))
    )
    (net (code "19") (name "GND") (class "Default")
      (node (ref "C1") (pin "1") (pinfunction "1_1") (pintype "passive"))
      (node (ref "C10") (pin "1") (pinfunction "1_1") (pintype "passive"))
      (node (ref "C11") (pin "1") (pinfunction "1_1") (pintype "passive"))
      (node (ref "C12") (pin "2") (pinfunction "2_2") (pintype "passive"))
      (node (ref "C13") (pin "1") (pinfunction "1_1") (pintype "passive"))
      (node (ref "C14") (pin "1") (pinfunction "1_1") (pintype "passive"))
      (node (ref "C15") (pin "1") (pinfunction "1_1") (pintype "passive"))
      (node (ref "C16") (pin "1") (pinfunction "1_1") (pintype "passive"))
      (node (ref "C17") (pin "1") (pinfunction "1_1") (pintype "passive"))
      (node (ref "C18") (pin "2") (pinfunction "2_2") (pintype "passive"))
      (node (ref "C19") (pin "1") (pinfunction "1_1") (pintype "passive"))
      (node (ref "C2") (pin "1") (pinfunction "1_1") (pintype "passive"))
      (node (ref "C20") (pin "1") (pinfunction "1_1") (pintype "passive"))
      (node (ref "C21") (pin "1") (pinfunction "1_1") (pintype "passive"))
      (node (ref "C22") (pin "1") (pinfunction "1_1") (pintype "passive"))
      (node (ref "C23") (pin "1") (pinfunction "1_1") (pintype "passive"))
      (node (ref "C24") (pin "1") (pinfunction "1_1") (pintype "passive"))
      (node (ref "C3") (pin "2") (pinfunction "2_2") (pintype "passive"))
      (node (ref "C4") (pin "1") (pinfunction "1_1") (pintype "passive"))
      (node (ref "C5") (pin "1") (pinfunction "1_1") (pintype "passive"))
      (node (ref "C6") (pin "1") (pinfunction "1_1") (pintype "passive"))
      (node (ref "C7") (pin "1") (pinfunction "1_1") (pintype "passive"))
      (node (ref "C8") (pin "1") (pinfunction "1_1") (pintype "passive"))
      (node (ref "C9") (pin "1") (pinfunction "1_1") (pintype "passive"))
      (node (ref "D1") (pin "1") (pinfunction "Anode_1") (pintype "passive"))
      (node (ref "D10") (pin "1") (pinfunction "ANODE_1") (pintype "passive"))
      (node (ref "D11") (pin "1") (pinfunction "ANODE_1") (pintype "passive"))
      (node (ref "D12") (pin "1") (pinfunction "ANODE_1") (pintype "passive"))
      (node (ref "D13") (pin "1") (pinfunction "ANODE_1") (pintype "passive"))
      (node (ref "D14") (pin "1") (pinfunction "ANODE_1") (pintype "passive"))
      (node (ref "D15") (pin "1") (pinfunction "ANODE_1") (pintype "passive"))
      (node (ref "D4") (pin "1") (pinfunction "ANODE_1") (pintype "passive"))
      (node (ref "D5") (pin "1") (pinfunction "ANODE_1") (pintype "passive"))
      (node (ref "D7") (pin "1") (pinfunction "ANODE_1") (pintype "passive"))
      (node (ref "GND") (pin "1") (pinfunction "1_1") (pintype "passive"))
      (node (ref "J1") (pin "1") (pinfunction "1_1") (pintype "passive"))
      (node (ref "J3") (pin "1") (pinfunction "1_1") (pintype "passive"))
      (node (ref "R19") (pin "2") (pinfunction "2_2") (pintype "passive"))
      (node (ref "R20") (pin "2") (pinfunction "2_2") (pintype "passive"))
      (node (ref "R25") (pin "2") (pinfunction "2_2") (pintype "passive"))
      (node (ref "R26") (pin "2") (pinfunction "2_2") (pintype "passive"))
      (node (ref "R30") (pin "1") (pinfunction "1_1") (pintype "passive"))
      (node (ref "R7") (pin "1") (pinfunction "1_1") (pintype "passive"))
      (node (ref "U1") (pin "7") (pinfunction "VSS_7") (pintype "passive"))
      (node (ref "U2") (pin "10") (pinfunction "VSS2_10") (pintype "passive"))
      (node (ref "U2") (pin "13") (pinfunction "TEST1_13") (pintype "passive"))
      (node (ref "U2") (pin "2") (pinfunction "VSS1_2") (pintype "passive"))
      (node (ref "U2") (pin "5") (pinfunction "TEST2_5") (pintype "passive"))
      (node (ref "U3") (pin "10") (pinfunction "GND_10") (pintype "passive"))
      (node (ref "U3") (pin "15") (pinfunction "EPAD_15") (pintype "passive"))
      (node (ref "U3") (pin "4") (pinfunction "SYNC_4") (pintype "passive"))
      (node (ref "U3") (pin "9") (pinfunction "GND_9") (pintype "passive"))
    )
    (net (code "20") (name "Net-(C13-Pad2)") (class "Default")
      (node (ref "C13") (pin "2") (pinfunction "2_2") (pintype "passive"))
      (node (ref "R4") (pin "1") (pinfunction "1_1") (pintype "passive"))
    )
    (net (code "21") (name "Net-(D1-Cathode)") (class "Default")
      (node (ref "D1") (pin "2") (pinfunction "Cathode_2") (pintype "passive"))
      (node (ref "L1") (pin "1") (pinfunction "1_1") (pintype "passive"))
      (node (ref "R4") (pin "2") (pinfunction "2_2") (pintype "passive"))
      (node (ref "U3") (pin "11") (pinfunction "SWO_11") (pintype "passive"))
    )
    (net (code "22") (name "Net-(D2-ANODE)") (class "Default")
      (node (ref "D2") (pin "2") (pinfunction "ANODE_2") (pintype "passive"))
      (node (ref "U9") (pin "3") (pinfunction "D2_3") (pintype "passive"))
    )
    (net (code "23") (name "Net-(D2-CATHODE)") (class "Default")
      (node (ref "D2") (pin "1") (pinfunction "CATHODE_1") (pintype "passive"))
      (node (ref "R17") (pin "1") (pinfunction "1_1") (pintype "passive"))
    )
    (net (code "24") (name "Net-(D3-ANODE)") (class "Default")
      (node (ref "D3") (pin "2") (pinfunction "ANODE_2") (pintype "passive"))
      (node (ref "U10") (pin "3") (pinfunction "D2_3") (pintype "passive"))
    )
    (net (code "25") (name "Net-(D3-CATHODE)") (class "Default")
      (node (ref "D3") (pin "1") (pinfunction "CATHODE_1") (pintype "passive"))
      (node (ref "R18") (pin "1") (pinfunction "1_1") (pintype "passive"))
    )
    (net (code "26") (name "Net-(D6-Anode)") (class "Default")
      (node (ref "D6") (pin "1") (pinfunction "Anode_1") (pintype "passive"))
      (node (ref "D7") (pin "2") (pinfunction "CATHODE_2") (pintype "passive"))
      (node (ref "J3") (pin "3") (pinfunction "3_3") (pintype "passive"))
      (node (ref "VCC") (pin "1") (pinfunction "1_1") (pintype "passive"))
    )
    (net (code "27") (name "Net-(D8-ANODE)") (class "Default")
      (node (ref "D8") (pin "2") (pinfunction "ANODE_2") (pintype "passive"))
      (node (ref "U9") (pin "6") (pinfunction "D1_6") (pintype "passive"))
    )
    (net (code "28") (name "Net-(D8-CATHODE)") (class "Default")
      (node (ref "D8") (pin "1") (pinfunction "CATHODE_1") (pintype "passive"))
      (node (ref "R23") (pin "1") (pinfunction "1_1") (pintype "passive"))
    )
    (net (code "29") (name "Net-(D9-ANODE)") (class "Default")
      (node (ref "D9") (pin "2") (pinfunction "ANODE_2") (pintype "passive"))
      (node (ref "U10") (pin "6") (pinfunction "D1_6") (pintype "passive"))
    )
    (net (code "30") (name "Net-(D9-CATHODE)") (class "Default")
      (node (ref "D9") (pin "1") (pinfunction "CATHODE_1") (pintype "passive"))
      (node (ref "R24") (pin "1") (pinfunction "1_1") (pintype "passive"))
    )
    (net (code "31") (name "Net-(D15-CATHODE)") (class "Default")
      (node (ref "D15") (pin "2") (pinfunction "CATHODE_2") (pintype "passive"))
      (node (ref "J1") (pin "3") (pinfunction "3_3") (pintype "passive"))
      (node (ref "R6") (pin "1") (pinfunction "1_1") (pintype "passive"))
    )
    (net (code "32") (name "Net-(U1-PA3_(HS){slash}[SPI_NSS]_TIM5_CH3)") (class "Default")
      (node (ref "R3") (pin "2") (pinfunction "2_2") (pintype "passive"))
      (node (ref "U1") (pin "10") (pinfunction "PA3_(HS)/[SPI_NSS]_TIM5_CH3_10") (pintype "passive"))
    )
    (net (code "33") (name "Net-(U1-VCAP)") (class "Default")
      (node (ref "C3") (pin "1") (pinfunction "1_1") (pintype "passive"))
      (node (ref "U1") (pin "8") (pinfunction "VCAP_8") (pintype "passive"))
    )
    (net (code "34") (name "Net-(U2-VDEC1)") (class "Default")
      (node (ref "C8") (pin "2") (pinfunction "2_2") (pintype "passive"))
      (node (ref "C9") (pin "2") (pinfunction "2_2") (pintype "passive"))
      (node (ref "U2") (pin "1") (pinfunction "VDEC1_1") (pintype "passive"))
      (node (ref "U2") (pin "9") (pinfunction "VDEC2_9") (pintype "passive"))
    )
    (net (code "35") (name "Net-(U3-EN)") (class "Default")
      (node (ref "R15") (pin "1") (pinfunction "1_1") (pintype "passive"))
      (node (ref "U3") (pin "14") (pinfunction "EN_14") (pintype "passive"))
    )
    (net (code "36") (name "Net-(U3-FB)") (class "Default")
      (node (ref "C4") (pin "2") (pinfunction "2_2") (pintype "passive"))
      (node (ref "C5") (pin "2") (pinfunction "2_2") (pintype "passive"))
      (node (ref "FB1") (pin "1") (pinfunction "1_1") (pintype "passive"))
      (node (ref "L1") (pin "2") (pinfunction "2_2") (pintype "passive"))
      (node (ref "U3") (pin "7") (pinfunction "FB_7") (pintype "passive"))
    )
    (net (code "37") (name "Net-(U3-FREQ)") (class "Default")
      (node (ref "R7") (pin "2") (pinfunction "2_2") (pintype "passive"))
      (node (ref "U3") (pin "5") (pinfunction "FREQ_5") (pintype "passive"))
    )
    (net (code "38") (name "VCC_5V") (class "Default")
      (node (ref "5V") (pin "1") (pinfunction "1_1") (pintype "passive"))
      (node (ref "C10") (pin "2") (pinfunction "2_2") (pintype "passive"))
      (node (ref "C14") (pin "2") (pinfunction "2_2") (pintype "passive"))
      (node (ref "C15") (pin "2") (pinfunction "2_2") (pintype "passive"))
      (node (ref "C16") (pin "2") (pinfunction "2_2") (pintype "passive"))
      (node (ref "C17") (pin "2") (pinfunction "2_2") (pintype "passive"))
      (node (ref "C2") (pin "2") (pinfunction "2_2") (pintype "passive"))
      (node (ref "C21") (pin "2") (pinfunction "2_2") (pintype "passive"))
      (node (ref "C7") (pin "2") (pinfunction "2_2") (pintype "passive"))
      (node (ref "FB1") (pin "2") (pinfunction "2_2") (pintype "passive"))
      (node (ref "J1") (pin "2") (pinfunction "2_2") (pintype "power_in"))
      (node (ref "R1") (pin "2") (pinfunction "2_2") (pintype "passive"))
      (node (ref "R2") (pin "2") (pinfunction "2_2") (pintype "passive"))
      (node (ref "R27") (pin "2") (pinfunction "2_2") (pintype "passive"))
      (node (ref "R28") (pin "2") (pinfunction "2_2") (pintype "passive"))
      (node (ref "R29") (pin "2") (pinfunction "2_2") (pintype "passive"))
      (node (ref "R5") (pin "2") (pinfunction "2_2") (pintype "passive"))
      (node (ref "U1") (pin "9") (pinfunction "VDD_9") (pintype "passive"))
      (node (ref "U10") (pin "1") (pinfunction "S1_1") (pintype "passive"))
      (node (ref "U10") (pin "4") (pinfunction "S2_4") (pintype "passive"))
      (node (ref "U2") (pin "11") (pinfunction "VDD2_11") (pintype "passive"))
      (node (ref "U2") (pin "3") (pinfunction "VDD1_3") (pintype "passive"))
      (node (ref "U9") (pin "1") (pinfunction "S1_1") (pintype "passive"))
      (node (ref "U9") (pin "4") (pinfunction "S2_4") (pintype "passive"))
    )
    (net (code "39") (name "VCC_IN") (class "Default")
      (node (ref "C1") (pin "2") (pinfunction "2_2") (pintype "passive"))
      (node (ref "C11") (pin "2") (pinfunction "2_2") (pintype "passive"))
      (node (ref "C12") (pin "1") (pinfunction "1_1") (pintype "passive"))
      (node (ref "C18") (pin "1") (pinfunction "1_1") (pintype "passive"))
      (node (ref "C24") (pin "2") (pinfunction "2_2") (pintype "passive"))
      (node (ref "D6") (pin "2") (pinfunction "Cathode_2") (pintype "passive"))
      (node (ref "R15") (pin "2") (pinfunction "2_2") (pintype "passive"))
      (node (ref "U3") (pin "13") (pinfunction "VS_13") (pintype "passive"))
    )
    (net (code "40") (name "unconnected-(FID1-Pad0)") (class "Default")
      (node (ref "FID1") (pin "0") (pinfunction "0_0") (pintype "passive+no_connect"))
    )
    (net (code "41") (name "unconnected-(FID2-Pad0)") (class "Default")
      (node (ref "FID2") (pin "0") (pinfunction "0_0") (pintype "passive+no_connect"))
    )
    (net (code "42") (name "unconnected-(FID3-Pad0)") (class "Default")
      (node (ref "FID3") (pin "0") (pinfunction "0_0") (pintype "passive+no_connect"))
    )
    (net (code "43") (name "unconnected-(FID4-Pad0)") (class "Default")
      (node (ref "FID4") (pin "0") (pinfunction "0_0") (pintype "passive+no_connect"))
    )
    (net (code "44") (name "unconnected-(U1-PA1{slash}OSCIN-Pad5)") (class "Default")
      (node (ref "U1") (pin "5") (pinfunction "PA1/OSCIN_5") (pintype "passive+no_connect"))
    )
    (net (code "45") (name "unconnected-(U1-PA2{slash}OSCOUT-Pad6)") (class "Default")
      (node (ref "U1") (pin "6") (pinfunction "PA2/OSCOUT_6") (pintype "passive+no_connect"))
    )
    (net (code "46") (name "unconnected-(U3-N.C.-Pad1)") (class "Default")
      (node (ref "U3") (pin "1") (pinfunction "N.C._1") (pintype "passive+no_connect"))
    )
    (net (code "47") (name "unconnected-(U3-N.C.-Pad2)") (class "Default")
      (node (ref "U3") (pin "2") (pinfunction "N.C._2") (pintype "passive+no_connect"))
    )
    (net (code "48") (name "unconnected-(U3-N.C.-Pad3)") (class "Default")
      (node (ref "U3") (pin "3") (pinfunction "N.C._3") (pintype "passive+no_connect"))
    )
    (net (code "49") (name "unconnected-(U3-N.C.-Pad6)") (class "Default")
      (node (ref "U3") (pin "6") (pinfunction "N.C._6") (pintype "passive+no_connect"))
    )
    (net (code "50") (name "unconnected-(U3-N.C.-Pad8)") (class "Default")
      (node (ref "U3") (pin "8") (pinfunction "N.C._8") (pintype "passive+no_connect"))
    )
    (net (code "51") (name "unconnected-(U3-N.C.-Pad12)") (class "Default")
      (node (ref "U3") (pin "12") (pinfunction "N.C._12") (pintype "passive+no_connect"))
    )
  )
)
